# schematic.net
KiCad netlist of a schematic drawn in EAGLE
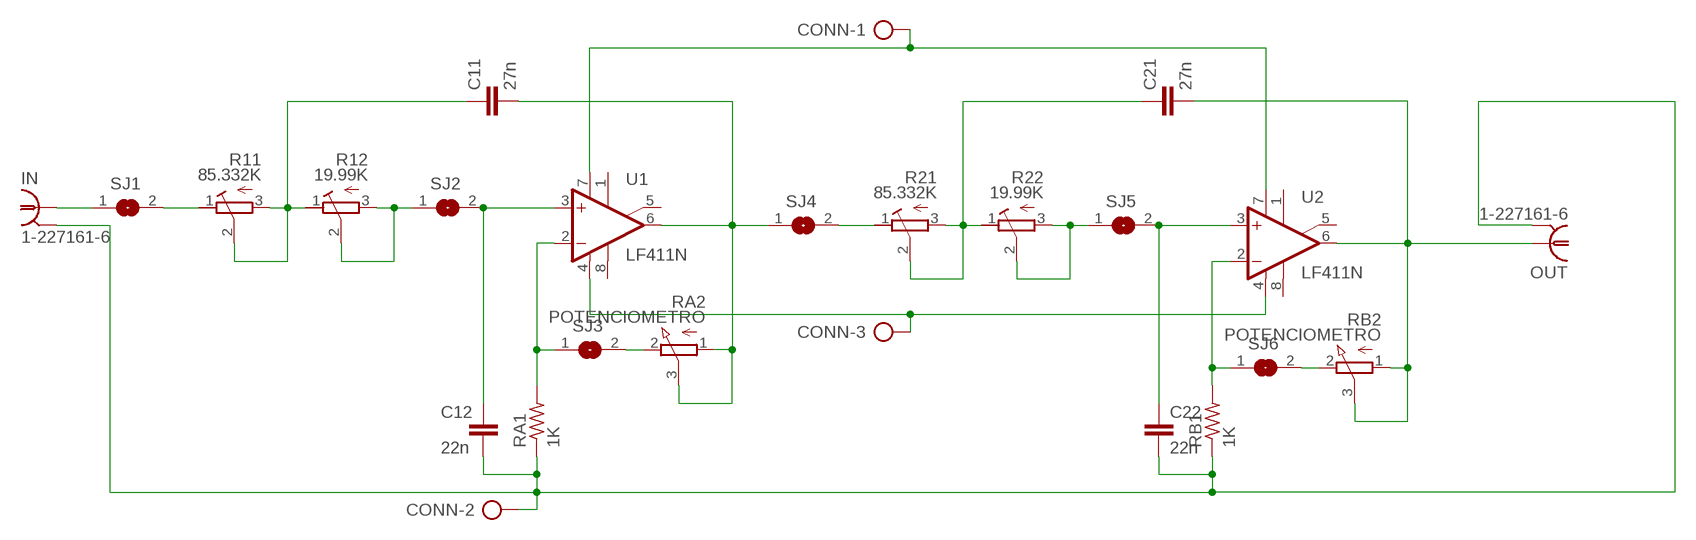
[diagram p0: schematic, sheet 1]

(export (version "E")
  (design (tool "Eeschema 10.0.6"))
  (components
    (comp (ref "C11")
      (value "27n")
      (footprint "eagle-import:C050-025X075")
      (libsource (lib "eagle-import") (part "C-EU050-025X075"))
    )
    (comp (ref "C12")
      (value "22n")
      (footprint "eagle-import:C050-025X075")
      (libsource (lib "eagle-import") (part "C-EU050-025X075"))
    )
    (comp (ref "C21")
      (value "27n")
      (footprint "eagle-import:C050-025X075")
      (libsource (lib "eagle-import") (part "C-EU050-025X075"))
    )
    (comp (ref "C22")
      (value "22n")
      (footprint "eagle-import:C050-025X075")
      (libsource (lib "eagle-import") (part "C-EU050-025X075"))
    )
    (comp (ref "CONN")
      (value "AK500/3")
      (footprint "eagle-import:AK500_3")
      (libsource (lib "eagle-import") (part "AK500/3"))
    )
    (comp (ref "IN")
      (value "1-227161-6")
      (footprint "eagle-import:AMP_227161")
      (fields (field (name "MF") "TYCO ELECTRONICS"))
      (libsource (lib "eagle-import") (part "?2271611--6"))
    )
    (comp (ref "OUT")
      (value "1-227161-6")
      (footprint "eagle-import:AMP_227161")
      (fields (field (name "MF") "TYCO ELECTRONICS"))
      (libsource (lib "eagle-import") (part "?2271611--6"))
    )
    (comp (ref "R11")
      (value "85.332K")
      (footprint "eagle-import:RTRIMT93YB")
      (libsource (lib "eagle-import") (part "R-TRIMMT93YB"))
    )
    (comp (ref "R12")
      (value "19.99K")
      (footprint "eagle-import:RTRIMT93YB")
      (libsource (lib "eagle-import") (part "R-TRIMMT93YB"))
    )
    (comp (ref "R21")
      (value "85.332K")
      (footprint "eagle-import:RTRIMT93YB")
      (libsource (lib "eagle-import") (part "R-TRIMMT93YB"))
    )
    (comp (ref "R22")
      (value "19.99K")
      (footprint "eagle-import:RTRIMT93YB")
      (libsource (lib "eagle-import") (part "R-TRIMMT93YB"))
    )
    (comp (ref "RA1")
      (value "1K")
      (footprint "eagle-import:0207_10")
      (libsource (lib "eagle-import") (part "R-US_0207/10"))
    )
    (comp (ref "RA2")
      (value "POTENCIOMETRO")
      (footprint "eagle-import:TSM4YJ")
      (libsource (lib "eagle-import") (part "POTENCIOMETRO"))
    )
    (comp (ref "RB1")
      (value "1K")
      (footprint "eagle-import:0207_10")
      (libsource (lib "eagle-import") (part "R-US_0207/10"))
    )
    (comp (ref "RB2")
      (value "POTENCIOMETRO")
      (footprint "eagle-import:TSM4YJ")
      (libsource (lib "eagle-import") (part "POTENCIOMETRO"))
    )
    (comp (ref "SJ1")
      (value "SJW")
      (footprint "eagle-import:SJW")
      (libsource (lib "eagle-import") (part "SJW"))
    )
    (comp (ref "SJ2")
      (value "SJW")
      (footprint "eagle-import:SJW")
      (libsource (lib "eagle-import") (part "SJW"))
    )
    (comp (ref "SJ3")
      (value "SJW")
      (footprint "eagle-import:SJW")
      (libsource (lib "eagle-import") (part "SJW"))
    )
    (comp (ref "SJ4")
      (value "SJW")
      (footprint "eagle-import:SJW")
      (libsource (lib "eagle-import") (part "SJW"))
    )
    (comp (ref "SJ5")
      (value "SJW")
      (footprint "eagle-import:SJW")
      (libsource (lib "eagle-import") (part "SJW"))
    )
    (comp (ref "SJ6")
      (value "SJW")
      (footprint "eagle-import:SJW")
      (libsource (lib "eagle-import") (part "SJW"))
    )
    (comp (ref "U1")
      (value "LF411N")
      (footprint "eagle-import:DIL08")
      (libsource (lib "eagle-import") (part "LF411N"))
    )
    (comp (ref "U2")
      (value "LF411N")
      (footprint "eagle-import:DIL08")
      (libsource (lib "eagle-import") (part "LF411N"))
    )
  )
  (nets
    (net (code "1") (name "Net-(CONNA-KL)") (class "Default")
      (node (ref "CONN") (pin "1") (pinfunction "KL_1") (pintype "passive"))
      (node (ref "U1") (pin "7") (pinfunction "V+_7") (pintype "power_in"))
      (node (ref "U2") (pin "7") (pinfunction "V+_7") (pintype "power_in"))
    )
    (net (code "2") (name "Net-(CONNB-KL)") (class "Default")
      (node (ref "C12") (pin "2") (pinfunction "2_2") (pintype "passive"))
      (node (ref "C22") (pin "2") (pinfunction "2_2") (pintype "passive"))
      (node (ref "CONN") (pin "2") (pinfunction "KL_2") (pintype "passive"))
      (node (ref "IN") (pin "2") (pinfunction "2_2") (pintype "passive"))
      (node (ref "OUT") (pin "2") (pinfunction "2_2") (pintype "passive"))
      (node (ref "RA1") (pin "1") (pinfunction "1_1") (pintype "passive"))
      (node (ref "RB1") (pin "1") (pinfunction "1_1") (pintype "passive"))
    )
    (net (code "3") (name "Net-(CONNC-KL)") (class "Default")
      (node (ref "CONN") (pin "3") (pinfunction "KL_3") (pintype "passive"))
      (node (ref "U1") (pin "4") (pinfunction "V-_4") (pintype "power_in"))
      (node (ref "U2") (pin "4") (pinfunction "V-_4") (pintype "power_in"))
    )
    (net (code "4") (name "Net-(IN-Pad1)") (class "Default")
      (node (ref "IN") (pin "1") (pinfunction "1_1") (pintype "passive"))
      (node (ref "SJ1") (pin "1") (pinfunction "1_1") (pintype "passive"))
    )
    (net (code "5") (name "Net-(R11-A)") (class "Default")
      (node (ref "C11") (pin "1") (pinfunction "1_1") (pintype "passive"))
      (node (ref "R11") (pin "2") (pinfunction "S_2") (pintype "passive"))
      (node (ref "R11") (pin "3") (pinfunction "A_3") (pintype "passive"))
      (node (ref "R12") (pin "1") (pinfunction "E_1") (pintype "passive"))
    )
    (net (code "6") (name "Net-(R11-E)") (class "Default")
      (node (ref "R11") (pin "1") (pinfunction "E_1") (pintype "passive"))
      (node (ref "SJ1") (pin "2") (pinfunction "2_2") (pintype "passive"))
    )
    (net (code "7") (name "Net-(R12-A)") (class "Default")
      (node (ref "R12") (pin "2") (pinfunction "S_2") (pintype "passive"))
      (node (ref "R12") (pin "3") (pinfunction "A_3") (pintype "passive"))
      (node (ref "SJ2") (pin "1") (pinfunction "1_1") (pintype "passive"))
    )
    (net (code "8") (name "Net-(R21-A)") (class "Default")
      (node (ref "C21") (pin "1") (pinfunction "1_1") (pintype "passive"))
      (node (ref "R21") (pin "2") (pinfunction "S_2") (pintype "passive"))
      (node (ref "R21") (pin "3") (pinfunction "A_3") (pintype "passive"))
      (node (ref "R22") (pin "1") (pinfunction "E_1") (pintype "passive"))
    )
    (net (code "9") (name "Net-(R21-E)") (class "Default")
      (node (ref "R21") (pin "1") (pinfunction "E_1") (pintype "passive"))
      (node (ref "SJ4") (pin "2") (pinfunction "2_2") (pintype "passive"))
    )
    (net (code "10") (name "Net-(R22-A)") (class "Default")
      (node (ref "R22") (pin "2") (pinfunction "S_2") (pintype "passive"))
      (node (ref "R22") (pin "3") (pinfunction "A_3") (pintype "passive"))
      (node (ref "SJ5") (pin "1") (pinfunction "1_1") (pintype "passive"))
    )
    (net (code "11") (name "Net-(RA2-A)") (class "Default")
      (node (ref "C11") (pin "2") (pinfunction "2_2") (pintype "passive"))
      (node (ref "RA2") (pin "1") (pinfunction "A_1") (pintype "passive"))
      (node (ref "RA2") (pin "3") (pinfunction "S_3") (pintype "passive"))
      (node (ref "SJ4") (pin "1") (pinfunction "1_1") (pintype "passive"))
      (node (ref "U1") (pin "6") (pinfunction "OUT_6") (pintype "output"))
    )
    (net (code "12") (name "Net-(RA2-E)") (class "Default")
      (node (ref "RA2") (pin "2") (pinfunction "E_2") (pintype "passive"))
      (node (ref "SJ3") (pin "2") (pinfunction "2_2") (pintype "passive"))
    )
    (net (code "13") (name "Net-(RB2-A)") (class "Default")
      (node (ref "C21") (pin "2") (pinfunction "2_2") (pintype "passive"))
      (node (ref "OUT") (pin "1") (pinfunction "1_1") (pintype "passive"))
      (node (ref "RB2") (pin "1") (pinfunction "A_1") (pintype "passive"))
      (node (ref "RB2") (pin "3") (pinfunction "S_3") (pintype "passive"))
      (node (ref "U2") (pin "6") (pinfunction "OUT_6") (pintype "output"))
    )
    (net (code "14") (name "Net-(RB2-E)") (class "Default")
      (node (ref "RB2") (pin "2") (pinfunction "E_2") (pintype "passive"))
      (node (ref "SJ6") (pin "2") (pinfunction "2_2") (pintype "passive"))
    )
    (net (code "15") (name "Net-(U1-+IN)") (class "Default")
      (node (ref "C12") (pin "1") (pinfunction "1_1") (pintype "passive"))
      (node (ref "SJ2") (pin "2") (pinfunction "2_2") (pintype "passive"))
      (node (ref "U1") (pin "3") (pinfunction "+IN_3") (pintype "input"))
    )
    (net (code "16") (name "Net-(U1--IN)") (class "Default")
      (node (ref "RA1") (pin "2") (pinfunction "2_2") (pintype "passive"))
      (node (ref "SJ3") (pin "1") (pinfunction "1_1") (pintype "passive"))
      (node (ref "U1") (pin "2") (pinfunction "-IN_2") (pintype "input"))
    )
    (net (code "17") (name "Net-(U2-+IN)") (class "Default")
      (node (ref "C22") (pin "1") (pinfunction "1_1") (pintype "passive"))
      (node (ref "SJ5") (pin "2") (pinfunction "2_2") (pintype "passive"))
      (node (ref "U2") (pin "3") (pinfunction "+IN_3") (pintype "input"))
    )
    (net (code "18") (name "Net-(U2--IN)") (class "Default")
      (node (ref "RB1") (pin "2") (pinfunction "2_2") (pintype "passive"))
      (node (ref "SJ6") (pin "1") (pinfunction "1_1") (pintype "passive"))
      (node (ref "U2") (pin "2") (pinfunction "-IN_2") (pintype "input"))
    )
    (net (code "19") (name "unconnected-(U1-ON1-Pad1)") (class "Default")
      (node (ref "U1") (pin "1") (pinfunction "ON1_1") (pintype "passive"))
    )
    (net (code "20") (name "unconnected-(U1-ON2-Pad5)") (class "Default")
      (node (ref "U1") (pin "5") (pinfunction "ON2_5") (pintype "passive"))
    )
    (net (code "21") (name "unconnected-(U1-OPT-Pad8)") (class "Default")
      (node (ref "U1") (pin "8") (pinfunction "OPT_8") (pintype "passive"))
    )
    (net (code "22") (name "unconnected-(U2-ON1-Pad1)") (class "Default")
      (node (ref "U2") (pin "1") (pinfunction "ON1_1") (pintype "passive"))
    )
    (net (code "23") (name "unconnected-(U2-ON2-Pad5)") (class "Default")
      (node (ref "U2") (pin "5") (pinfunction "ON2_5") (pintype "passive"))
    )
    (net (code "24") (name "unconnected-(U2-OPT-Pad8)") (class "Default")
      (node (ref "U2") (pin "8") (pinfunction "OPT_8") (pintype "passive"))
    )
  )
)
